# MCU1_1.net
KiCad netlist of a schematic drawn in Altium Designer
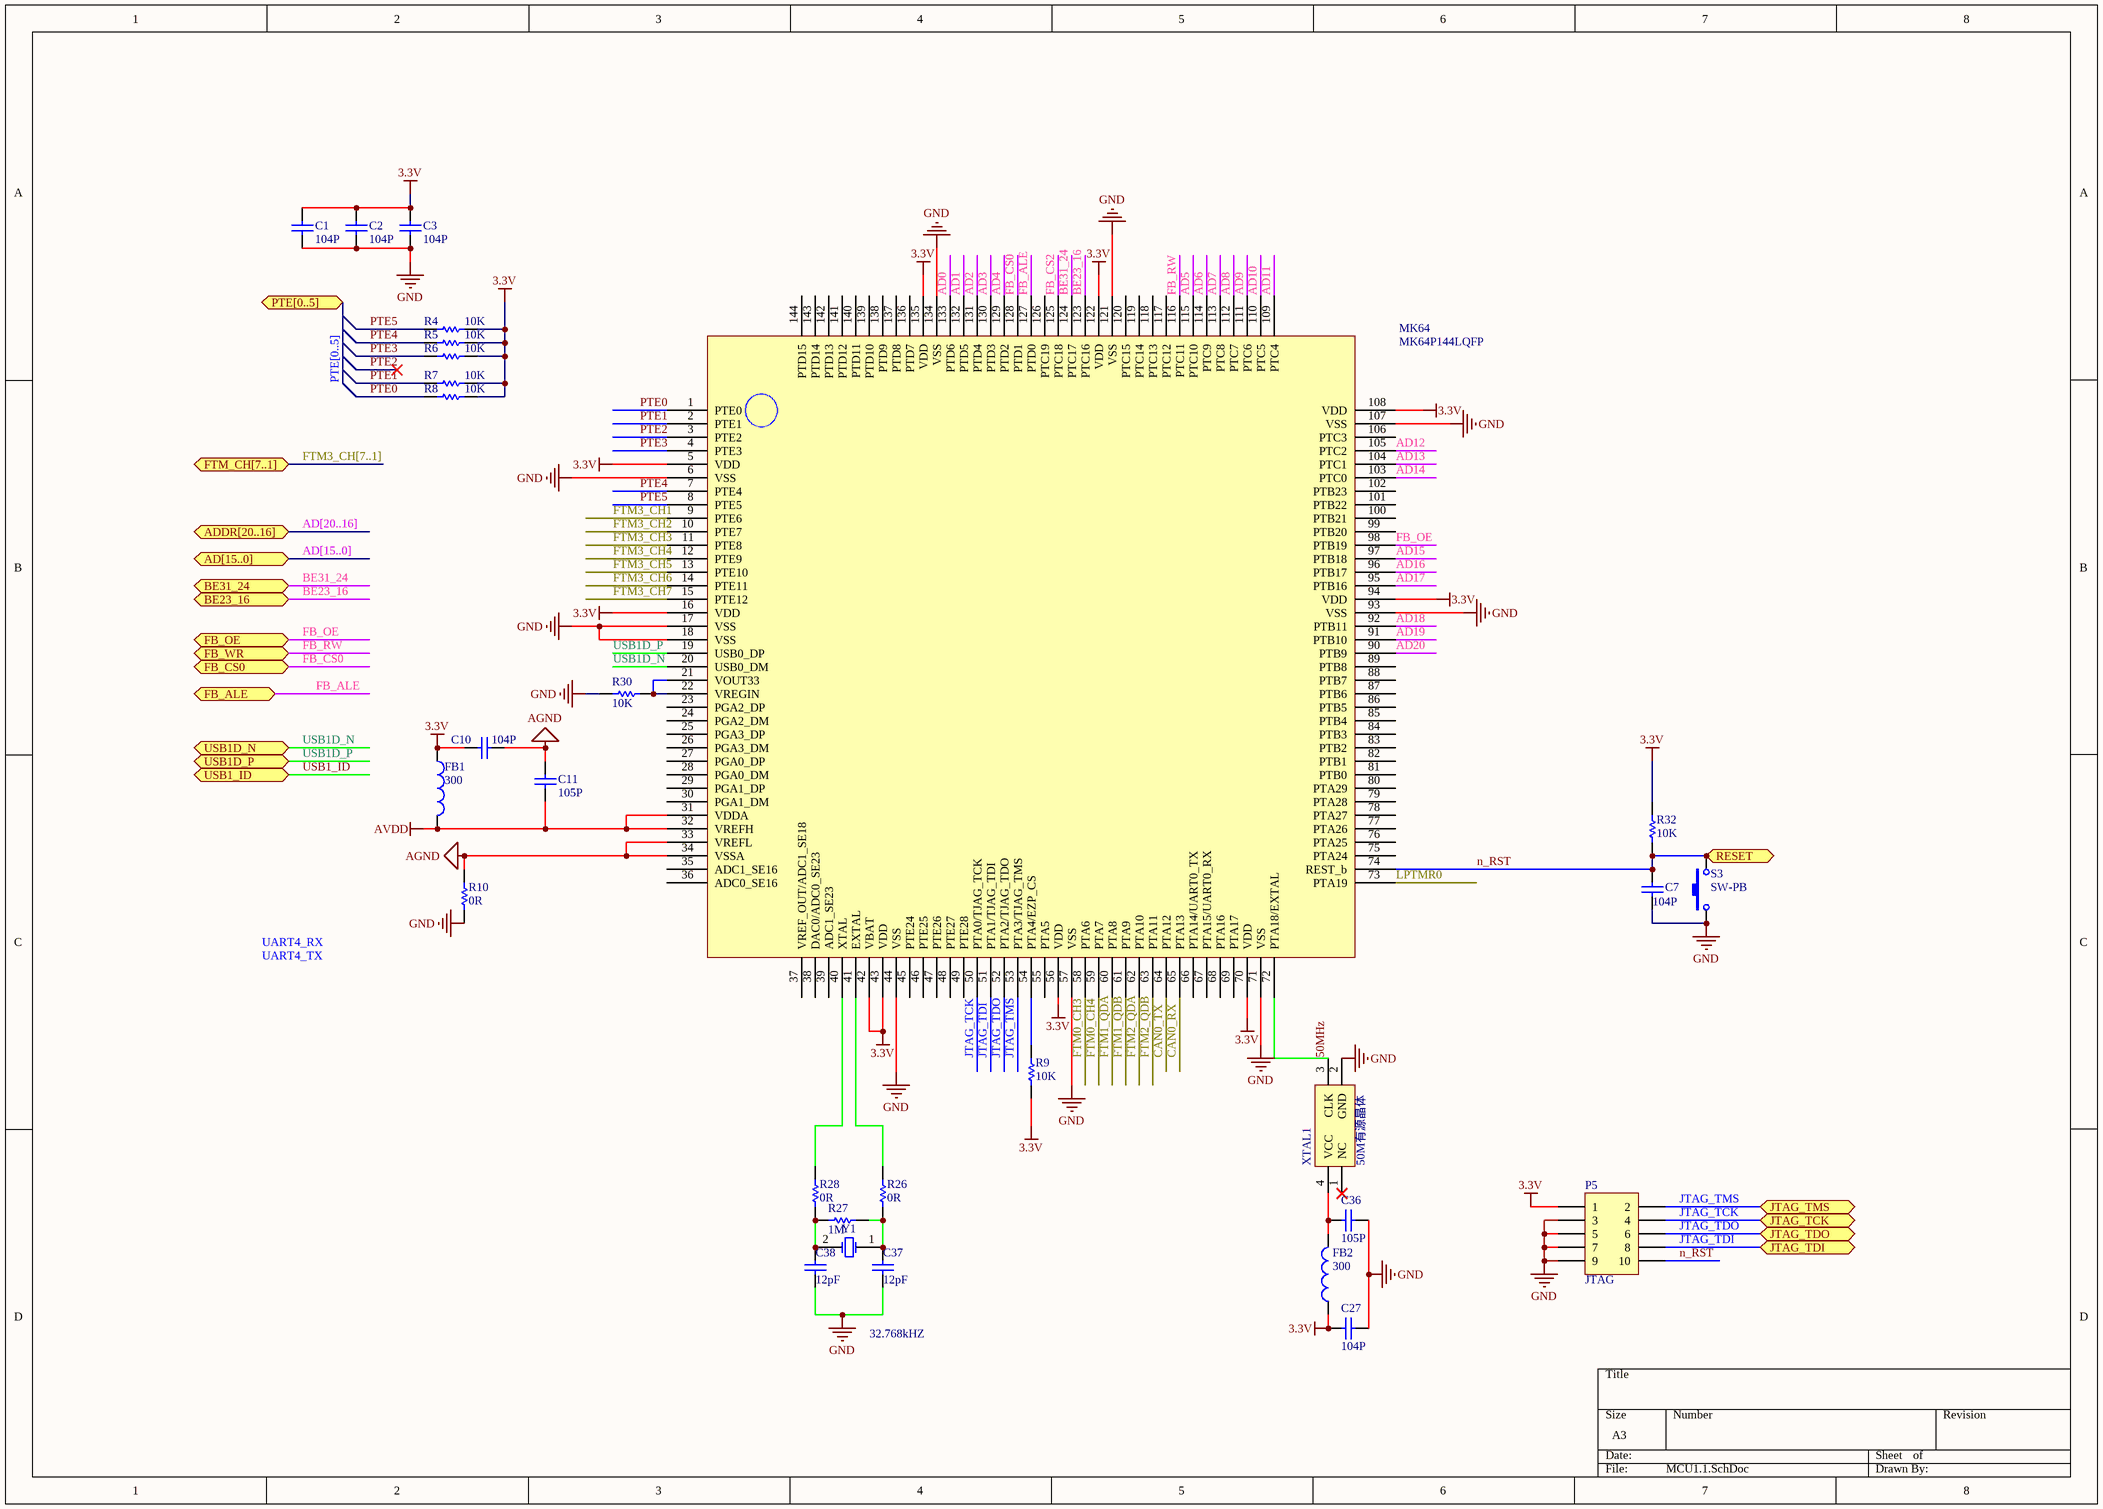
[diagram p0: MCU1.1.SchDoc]

(export (version "E")
  (design (tool "Eeschema 10.0.6"))
  (components
    (comp (ref "C1")
      (value "104P")
      (footprint "1608[0603]")
      (description "贴片电容")
      (fields (field (name "Comment") "Cap") (field (name "PUBLISHER") "Altium Limited"))
      (libsource (lib "Sparks") (part "Cap"))
    )
    (comp (ref "C2")
      (value "104P")
      (footprint "1608[0603]")
      (description "贴片电容")
      (fields (field (name "Comment") "Cap") (field (name "PUBLISHER") "Altium Limited"))
      (libsource (lib "Sparks") (part "Cap"))
    )
    (comp (ref "C3")
      (value "104P")
      (footprint "1608[0603]")
      (description "贴片电容")
      (fields (field (name "Comment") "Cap") (field (name "PUBLISHER") "Altium Limited"))
      (libsource (lib "Sparks") (part "Cap"))
    )
    (comp (ref "C7")
      (value "104P")
      (footprint "1608[0603]")
      (description "贴片电容")
      (fields (field (name "Comment") "Cap") (field (name "PUBLISHER") "Altium Limited"))
      (libsource (lib "Sparks") (part "Cap"))
    )
    (comp (ref "C10")
      (value "104P")
      (footprint "1608[0603]")
      (description "贴片电容")
      (fields (field (name "Comment") "Cap") (field (name "PUBLISHER") "Altium Limited"))
      (libsource (lib "Sparks") (part "Cap"))
    )
    (comp (ref "C11")
      (value "105P")
      (footprint "1608[0603]")
      (description "贴片电容")
      (fields (field (name "Comment") "Cap") (field (name "PUBLISHER") "Altium Limited"))
      (libsource (lib "Sparks") (part "Cap"))
    )
    (comp (ref "C27")
      (value "104P")
      (footprint "1608[0603]")
      (description "贴片电容")
      (fields (field (name "Comment") "Cap") (field (name "PUBLISHER") "Altium Limited"))
      (libsource (lib "Sparks") (part "Cap"))
    )
    (comp (ref "C36")
      (value "105P")
      (footprint "1608[0603]")
      (description "贴片电容")
      (fields (field (name "Comment") "Cap") (field (name "PUBLISHER") "Altium Limited"))
      (libsource (lib "Sparks") (part "Cap"))
    )
    (comp (ref "C37")
      (value "12pF")
      (footprint "1608[0603]")
      (description "贴片电容")
      (fields (field (name "Comment") "Cap") (field (name "PUBLISHER") "Altium Limited"))
      (libsource (lib "Sparks") (part "Cap"))
    )
    (comp (ref "C38")
      (value "12pF")
      (footprint "1608[0603]")
      (description "贴片电容")
      (fields (field (name "Comment") "Cap") (field (name "PUBLISHER") "Altium Limited"))
      (libsource (lib "Sparks") (part "Cap"))
    )
    (comp (ref "FB1")
      (value "300")
      (footprint "1608[0603]")
      (description "Inductor")
      (fields (field (name "PUBLISHER") "Altium Limited"))
      (libsource (lib "Miscellaneous Devices") (part "Inductor"))
    )
    (comp (ref "FB2")
      (value "300")
      (footprint "1608[0603]")
      (description "Inductor")
      (fields (field (name "PUBLISHER") "Altium Limited"))
      (libsource (lib "Miscellaneous Devices") (part "Inductor"))
    )
    (comp (ref "MK64")
      (value "MK64P144LQFP")
      (footprint "LQFP-144")
      (libsource (lib "2号库") (part "MK64P144LQFP"))
    )
    (comp (ref "P5")
      (value "JTAG")
      (footprint "HDR2X5")
      (description "Header, 5-Pin, Dual row")
      (fields (field (name "PUBLISHER") "Altium Limited"))
      (libsource (lib "Sparks") (part "Header 5X2"))
    )
    (comp (ref "R4")
      (value "10K")
      (footprint "1608[0603]")
      (description "贴片电阻")
      (fields (field (name "Comment") "Res") (field (name "PUBLISHER") "Altium Limited"))
      (libsource (lib "Sparks") (part "Res"))
    )
    (comp (ref "R5")
      (value "10K")
      (footprint "1608[0603]")
      (description "贴片电阻")
      (fields (field (name "Comment") "Res") (field (name "PUBLISHER") "Altium Limited"))
      (libsource (lib "Sparks") (part "Res"))
    )
    (comp (ref "R6")
      (value "10K")
      (footprint "1608[0603]")
      (description "贴片电阻")
      (fields (field (name "Comment") "Res") (field (name "PUBLISHER") "Altium Limited"))
      (libsource (lib "Sparks") (part "Res"))
    )
    (comp (ref "R7")
      (value "10K")
      (footprint "1608[0603]")
      (description "贴片电阻")
      (fields (field (name "Comment") "Res") (field (name "PUBLISHER") "Altium Limited"))
      (libsource (lib "Sparks") (part "Res"))
    )
    (comp (ref "R8")
      (value "10K")
      (footprint "1608[0603]")
      (description "贴片电阻")
      (fields (field (name "Comment") "Res") (field (name "PUBLISHER") "Altium Limited"))
      (libsource (lib "Sparks") (part "Res"))
    )
    (comp (ref "R9")
      (value "10K")
      (footprint "1608[0603]")
      (description "贴片电阻")
      (fields (field (name "Comment") "Res") (field (name "PUBLISHER") "Altium Limited"))
      (libsource (lib "Sparks") (part "Res"))
    )
    (comp (ref "R10")
      (value "0R")
      (footprint "1608[0603]")
      (description "贴片电阻")
      (fields (field (name "Comment") "Res") (field (name "PUBLISHER") "Altium Limited"))
      (libsource (lib "Sparks") (part "Res"))
    )
    (comp (ref "R26")
      (value "0R")
      (footprint "1608[0603]")
      (description "贴片电阻")
      (fields (field (name "Comment") "Res") (field (name "PUBLISHER") "Altium Limited"))
      (libsource (lib "Sparks") (part "Res"))
    )
    (comp (ref "R27")
      (value "1M")
      (footprint "1608[0603]")
      (description "贴片电阻")
      (fields (field (name "Comment") "Res") (field (name "PUBLISHER") "Altium Limited"))
      (libsource (lib "Sparks") (part "Res"))
    )
    (comp (ref "R28")
      (value "0R")
      (footprint "1608[0603]")
      (description "贴片电阻")
      (fields (field (name "Comment") "Res") (field (name "PUBLISHER") "Altium Limited"))
      (libsource (lib "Sparks") (part "Res"))
    )
    (comp (ref "R30")
      (value "10K")
      (footprint "1608[0603]")
      (description "贴片电阻")
      (fields (field (name "Comment") "Res") (field (name "PUBLISHER") "Altium Limited"))
      (libsource (lib "Sparks") (part "Res"))
    )
    (comp (ref "R32")
      (value "10K")
      (footprint "1608[0603]")
      (description "贴片电阻")
      (fields (field (name "Comment") "Res") (field (name "PUBLISHER") "Altium Limited"))
      (libsource (lib "Sparks") (part "Res"))
    )
    (comp (ref "S3")
      (value "SW-PB")
      (footprint "key 3*4*2")
      (description "Switch")
      (libsource (lib "K60-V4.0") (part "SW-PB"))
    )
    (comp (ref "XTAL1") (value "50M有源晶体") (footprint "XTAL7_3225") (libsource (lib "Sparks") (part "有源晶体")))
    (comp (ref "Y1")
      (value "32.768kHZ")
      (footprint "3215")
      (description "晶体振荡器")
      (fields (field (name "PUBLISHER") "Altium Limited"))
      (libsource (lib "Sparks") (part "XTAL"))
    )
  )
  (nets
    (net (code "1") (name "/50MHz") (class "Default")
      (node (ref "MK64") (pin "72") (pinfunction "PTA18/EXTAL_72") (pintype "passive"))
      (node (ref "XTAL1") (pin "3") (pinfunction "CLK_3") (pintype "passive"))
    )
    (net (code "2") (name "/AD0") (class "Default")
      (node (ref "MK64") (pin "133") (pinfunction "PTD6_133") (pintype "passive"))
    )
    (net (code "3") (name "/AD1") (class "Default")
      (node (ref "MK64") (pin "132") (pinfunction "PTD5_132") (pintype "passive"))
    )
    (net (code "4") (name "/AD2") (class "Default")
      (node (ref "MK64") (pin "131") (pinfunction "PTD4_131") (pintype "passive"))
    )
    (net (code "5") (name "/AD3") (class "Default")
      (node (ref "MK64") (pin "130") (pinfunction "PTD3_130") (pintype "passive"))
    )
    (net (code "6") (name "/AD4") (class "Default")
      (node (ref "MK64") (pin "129") (pinfunction "PTD2_129") (pintype "passive"))
    )
    (net (code "7") (name "/AD5") (class "Default")
      (node (ref "MK64") (pin "115") (pinfunction "PTC10_115") (pintype "passive"))
    )
    (net (code "8") (name "/AD6") (class "Default")
      (node (ref "MK64") (pin "114") (pinfunction "PTC9_114") (pintype "passive"))
    )
    (net (code "9") (name "/AD7") (class "Default")
      (node (ref "MK64") (pin "113") (pinfunction "PTC8_113") (pintype "passive"))
    )
    (net (code "10") (name "/AD8") (class "Default")
      (node (ref "MK64") (pin "112") (pinfunction "PTC7_112") (pintype "passive"))
    )
    (net (code "11") (name "/AD9") (class "Default")
      (node (ref "MK64") (pin "111") (pinfunction "PTC6_111") (pintype "passive"))
    )
    (net (code "12") (name "/AD10") (class "Default")
      (node (ref "MK64") (pin "110") (pinfunction "PTC5_110") (pintype "passive"))
    )
    (net (code "13") (name "/AD11") (class "Default")
      (node (ref "MK64") (pin "109") (pinfunction "PTC4_109") (pintype "passive"))
    )
    (net (code "14") (name "/AD12") (class "Default")
      (node (ref "MK64") (pin "105") (pinfunction "PTC2_105") (pintype "passive"))
    )
    (net (code "15") (name "/AD13") (class "Default")
      (node (ref "MK64") (pin "104") (pinfunction "PTC1_104") (pintype "passive"))
    )
    (net (code "16") (name "/AD14") (class "Default")
      (node (ref "MK64") (pin "103") (pinfunction "PTC0_103") (pintype "passive"))
    )
    (net (code "17") (name "/AD15") (class "Default")
      (node (ref "MK64") (pin "97") (pinfunction "PTB18_97") (pintype "passive"))
    )
    (net (code "18") (name "/AD16") (class "Default")
      (node (ref "MK64") (pin "96") (pinfunction "PTB17_96") (pintype "passive"))
    )
    (net (code "19") (name "/AD17") (class "Default")
      (node (ref "MK64") (pin "95") (pinfunction "PTB16_95") (pintype "passive"))
    )
    (net (code "20") (name "/AD18") (class "Default")
      (node (ref "MK64") (pin "92") (pinfunction "PTB11_92") (pintype "passive"))
    )
    (net (code "21") (name "/AD19") (class "Default")
      (node (ref "MK64") (pin "91") (pinfunction "PTB10_91") (pintype "passive"))
    )
    (net (code "22") (name "/AD20") (class "Default")
      (node (ref "MK64") (pin "90") (pinfunction "PTB9_90") (pintype "passive"))
    )
    (net (code "25") (name "/BE23_16") (class "Default")
      (node (ref "MK64") (pin "123") (pinfunction "PTC16_123") (pintype "passive"))
    )
    (net (code "26") (name "/BE31_24") (class "Default")
      (node (ref "MK64") (pin "124") (pinfunction "PTC17_124") (pintype "passive"))
    )
    (net (code "27") (name "/CAN0_RX") (class "Default")
      (node (ref "MK64") (pin "65") (pinfunction "PTA13_65") (pintype "passive"))
    )
    (net (code "28") (name "/CAN0_TX") (class "Default")
      (node (ref "MK64") (pin "64") (pinfunction "PTA12_64") (pintype "passive"))
    )
    (net (code "29") (name "/FB_ALE") (class "Default")
      (node (ref "MK64") (pin "127") (pinfunction "PTD0_127") (pintype "passive"))
    )
    (net (code "30") (name "/FB_CS0") (class "Default")
      (node (ref "MK64") (pin "128") (pinfunction "PTD1_128") (pintype "passive"))
    )
    (net (code "31") (name "/FB_CS2") (class "Default")
      (node (ref "MK64") (pin "125") (pinfunction "PTC18_125") (pintype "passive"))
    )
    (net (code "32") (name "/FB_OE") (class "Default")
      (node (ref "MK64") (pin "98") (pinfunction "PTB19_98") (pintype "passive"))
    )
    (net (code "33") (name "/FB_RW") (class "Default")
      (node (ref "MK64") (pin "116") (pinfunction "PTC11_116") (pintype "passive"))
    )
    (net (code "34") (name "/FTM0_CH3") (class "Default")
      (node (ref "MK64") (pin "58") (pinfunction "PTA6_58") (pintype "passive"))
    )
    (net (code "35") (name "/FTM0_CH4") (class "Default")
      (node (ref "MK64") (pin "59") (pinfunction "PTA7_59") (pintype "passive"))
    )
    (net (code "36") (name "/FTM1_QDA") (class "Default")
      (node (ref "MK64") (pin "60") (pinfunction "PTA8_60") (pintype "passive"))
    )
    (net (code "37") (name "/FTM1_QDB") (class "Default")
      (node (ref "MK64") (pin "61") (pinfunction "PTA9_61") (pintype "passive"))
    )
    (net (code "38") (name "/FTM2_QDA") (class "Default")
      (node (ref "MK64") (pin "62") (pinfunction "PTA10_62") (pintype "passive"))
    )
    (net (code "39") (name "/FTM2_QDB") (class "Default")
      (node (ref "MK64") (pin "63") (pinfunction "PTA11_63") (pintype "passive"))
    )
    (net (code "40") (name "/FTM3_CH1") (class "Default")
      (node (ref "MK64") (pin "9") (pinfunction "PTE6_9") (pintype "passive"))
    )
    (net (code "41") (name "/FTM3_CH2") (class "Default")
      (node (ref "MK64") (pin "10") (pinfunction "PTE7_10") (pintype "passive"))
    )
    (net (code "42") (name "/FTM3_CH3") (class "Default")
      (node (ref "MK64") (pin "11") (pinfunction "PTE8_11") (pintype "passive"))
    )
    (net (code "43") (name "/FTM3_CH4") (class "Default")
      (node (ref "MK64") (pin "12") (pinfunction "PTE9_12") (pintype "passive"))
    )
    (net (code "44") (name "/FTM3_CH5") (class "Default")
      (node (ref "MK64") (pin "13") (pinfunction "PTE10_13") (pintype "passive"))
    )
    (net (code "45") (name "/FTM3_CH6") (class "Default")
      (node (ref "MK64") (pin "14") (pinfunction "PTE11_14") (pintype "passive"))
    )
    (net (code "46") (name "/FTM3_CH7") (class "Default")
      (node (ref "MK64") (pin "15") (pinfunction "PTE12_15") (pintype "passive"))
    )
    (net (code "48") (name "/JTAG_TCK") (class "Default")
      (node (ref "MK64") (pin "50") (pinfunction "PTA0/TJAG_TCK_50") (pintype "passive"))
      (node (ref "P5") (pin "4") (pinfunction "4_4") (pintype "passive"))
    )
    (net (code "49") (name "/JTAG_TDI") (class "Default")
      (node (ref "MK64") (pin "51") (pinfunction "PTA1/TJAG_TDI_51") (pintype "passive"))
      (node (ref "P5") (pin "8") (pinfunction "8_8") (pintype "passive"))
    )
    (net (code "50") (name "/JTAG_TDO") (class "Default")
      (node (ref "MK64") (pin "52") (pinfunction "PTA2/TJAG_TDO_52") (pintype "passive"))
      (node (ref "P5") (pin "6") (pinfunction "6_6") (pintype "passive"))
    )
    (net (code "51") (name "/JTAG_TMS") (class "Default")
      (node (ref "MK64") (pin "53") (pinfunction "PTA3/TJAG_TMS_53") (pintype "passive"))
      (node (ref "P5") (pin "2") (pinfunction "2_2") (pintype "passive"))
    )
    (net (code "52") (name "/LPTMR0") (class "Default")
      (node (ref "MK64") (pin "73") (pinfunction "PTA19_73") (pintype "passive"))
    )
    (net (code "53") (name "/PTE0") (class "Default")
      (node (ref "MK64") (pin "1") (pinfunction "PTE0_1") (pintype "passive"))
      (node (ref "R8") (pin "2") (pinfunction "2_2") (pintype "passive"))
    )
    (net (code "54") (name "/PTE1") (class "Default")
      (node (ref "MK64") (pin "2") (pinfunction "PTE1_2") (pintype "passive"))
      (node (ref "R7") (pin "2") (pinfunction "2_2") (pintype "passive"))
    )
    (net (code "55") (name "/PTE2") (class "Default")
      (node (ref "MK64") (pin "3") (pinfunction "PTE2_3") (pintype "passive+no_connect"))
    )
    (net (code "56") (name "/PTE3") (class "Default")
      (node (ref "MK64") (pin "4") (pinfunction "PTE3_4") (pintype "passive"))
      (node (ref "R6") (pin "2") (pinfunction "2_2") (pintype "passive"))
    )
    (net (code "57") (name "/PTE4") (class "Default")
      (node (ref "MK64") (pin "7") (pinfunction "PTE4_7") (pintype "passive"))
      (node (ref "R5") (pin "2") (pinfunction "2_2") (pintype "passive"))
    )
    (net (code "58") (name "/PTE5") (class "Default")
      (node (ref "MK64") (pin "8") (pinfunction "PTE5_8") (pintype "passive"))
      (node (ref "R4") (pin "2") (pinfunction "2_2") (pintype "passive"))
    )
    (net (code "62") (name "/USB1D_N") (class "Default")
      (node (ref "MK64") (pin "20") (pinfunction "USB0_DM_20") (pintype "passive"))
    )
    (net (code "63") (name "/USB1D_P") (class "Default")
      (node (ref "MK64") (pin "19") (pinfunction "USB0_DP_19") (pintype "passive"))
    )
    (net (code "65") (name "/n_RST") (class "Default")
      (node (ref "C7") (pin "2") (pinfunction "2_2") (pintype "passive"))
      (node (ref "MK64") (pin "74") (pinfunction "REST_b_74") (pintype "passive"))
      (node (ref "P5") (pin "10") (pinfunction "10_10") (pintype "passive"))
      (node (ref "R32") (pin "2") (pinfunction "2_2") (pintype "passive"))
      (node (ref "S3") (pin "2") (pinfunction "2_2") (pintype "passive"))
    )
    (net (code "66") (name "3.3V") (class "Default")
      (node (ref "C1") (pin "2") (pinfunction "2_2") (pintype "passive"))
      (node (ref "C10") (pin "1") (pinfunction "1_1") (pintype "passive"))
      (node (ref "C2") (pin "2") (pinfunction "2_2") (pintype "passive"))
      (node (ref "C27") (pin "2") (pinfunction "2_2") (pintype "passive"))
      (node (ref "C3") (pin "2") (pinfunction "2_2") (pintype "passive"))
      (node (ref "FB1") (pin "1") (pinfunction "1_1") (pintype "passive"))
      (node (ref "FB2") (pin "1") (pinfunction "1_1") (pintype "passive"))
      (node (ref "MK64") (pin "108") (pinfunction "VDD_108") (pintype "passive"))
      (node (ref "MK64") (pin "122") (pinfunction "VDD_122") (pintype "passive"))
      (node (ref "MK64") (pin "135") (pinfunction "VDD_135") (pintype "passive"))
      (node (ref "MK64") (pin "16") (pinfunction "VDD_16") (pintype "passive"))
      (node (ref "MK64") (pin "42") (pinfunction "VBAT_42") (pintype "passive"))
      (node (ref "MK64") (pin "43") (pinfunction "VDD_43") (pintype "passive"))
      (node (ref "MK64") (pin "5") (pinfunction "VDD_5") (pintype "passive"))
      (node (ref "MK64") (pin "56") (pinfunction "VDD_56") (pintype "passive"))
      (node (ref "MK64") (pin "70") (pinfunction "VDD_70") (pintype "passive"))
      (node (ref "MK64") (pin "94") (pinfunction "VDD_94") (pintype "passive"))
      (node (ref "P5") (pin "1") (pinfunction "1_1") (pintype "passive"))
      (node (ref "R32") (pin "1") (pinfunction "1_1") (pintype "passive"))
      (node (ref "R4") (pin "1") (pinfunction "1_1") (pintype "passive"))
      (node (ref "R5") (pin "1") (pinfunction "1_1") (pintype "passive"))
      (node (ref "R6") (pin "1") (pinfunction "1_1") (pintype "passive"))
      (node (ref "R7") (pin "1") (pinfunction "1_1") (pintype "passive"))
      (node (ref "R8") (pin "1") (pinfunction "1_1") (pintype "passive"))
      (node (ref "R9") (pin "1") (pinfunction "1_1") (pintype "passive"))
    )
    (net (code "67") (name "AGND") (class "Default")
      (node (ref "C10") (pin "2") (pinfunction "2_2") (pintype "passive"))
      (node (ref "C11") (pin "2") (pinfunction "2_2") (pintype "passive"))
      (node (ref "MK64") (pin "33") (pinfunction "VREFL_33") (pintype "passive"))
      (node (ref "MK64") (pin "34") (pinfunction "VSSA_34") (pintype "passive"))
      (node (ref "R10") (pin "2") (pinfunction "2_2") (pintype "passive"))
    )
    (net (code "68") (name "AVDD") (class "Default")
      (node (ref "C11") (pin "1") (pinfunction "1_1") (pintype "passive"))
      (node (ref "FB1") (pin "2") (pinfunction "2_2") (pintype "passive"))
      (node (ref "MK64") (pin "31") (pinfunction "VDDA_31") (pintype "passive"))
      (node (ref "MK64") (pin "32") (pinfunction "VREFH_32") (pintype "passive"))
    )
    (net (code "69") (name "GND") (class "Default")
      (node (ref "C1") (pin "1") (pinfunction "1_1") (pintype "passive"))
      (node (ref "C2") (pin "1") (pinfunction "1_1") (pintype "passive"))
      (node (ref "C27") (pin "1") (pinfunction "1_1") (pintype "passive"))
      (node (ref "C3") (pin "1") (pinfunction "1_1") (pintype "passive"))
      (node (ref "C36") (pin "1") (pinfunction "1_1") (pintype "passive"))
      (node (ref "C37") (pin "1") (pinfunction "1_1") (pintype "passive"))
      (node (ref "C38") (pin "1") (pinfunction "1_1") (pintype "passive"))
      (node (ref "C7") (pin "1") (pinfunction "1_1") (pintype "passive"))
      (node (ref "MK64") (pin "107") (pinfunction "VSS_107") (pintype "passive"))
      (node (ref "MK64") (pin "121") (pinfunction "VSS_121") (pintype "passive"))
      (node (ref "MK64") (pin "134") (pinfunction "VSS_134") (pintype "passive"))
      (node (ref "MK64") (pin "17") (pinfunction "VSS_17") (pintype "passive"))
      (node (ref "MK64") (pin "18") (pinfunction "VSS_18") (pintype "passive"))
      (node (ref "MK64") (pin "44") (pinfunction "VSS_44") (pintype "passive"))
      (node (ref "MK64") (pin "57") (pinfunction "VSS_57") (pintype "passive"))
      (node (ref "MK64") (pin "6") (pinfunction "VSS_6") (pintype "passive"))
      (node (ref "MK64") (pin "71") (pinfunction "VSS_71") (pintype "passive"))
      (node (ref "MK64") (pin "93") (pinfunction "VSS_93") (pintype "passive"))
      (node (ref "P5") (pin "3") (pinfunction "3_3") (pintype "passive"))
      (node (ref "P5") (pin "5") (pinfunction "5_5") (pintype "passive"))
      (node (ref "P5") (pin "7") (pinfunction "7_7") (pintype "passive"))
      (node (ref "P5") (pin "9") (pinfunction "9_9") (pintype "passive"))
      (node (ref "R10") (pin "1") (pinfunction "1_1") (pintype "passive"))
      (node (ref "R30") (pin "1") (pinfunction "1_1") (pintype "passive"))
      (node (ref "S3") (pin "1") (pinfunction "1_1") (pintype "passive"))
      (node (ref "XTAL1") (pin "2") (pinfunction "GND_2") (pintype "passive"))
    )
    (net (code "70") (name "Net-(MK64-EXTAL)") (class "Default")
      (node (ref "MK64") (pin "41") (pinfunction "EXTAL_41") (pintype "passive"))
      (node (ref "R26") (pin "2") (pinfunction "2_2") (pintype "passive"))
    )
    (net (code "71") (name "Net-(MK64-PTA4{slash}EZP_CS)") (class "Default")
      (node (ref "MK64") (pin "54") (pinfunction "PTA4/EZP_CS_54") (pintype "passive"))
      (node (ref "R9") (pin "2") (pinfunction "2_2") (pintype "passive"))
    )
    (net (code "72") (name "Net-(MK64-VOUT33)") (class "Default")
      (node (ref "MK64") (pin "21") (pinfunction "VOUT33_21") (pintype "passive"))
      (node (ref "MK64") (pin "22") (pinfunction "VREGIN_22") (pintype "passive"))
      (node (ref "R30") (pin "2") (pinfunction "2_2") (pintype "passive"))
    )
    (net (code "73") (name "Net-(MK64-XTAL)") (class "Default")
      (node (ref "MK64") (pin "40") (pinfunction "XTAL_40") (pintype "passive"))
      (node (ref "R28") (pin "2") (pinfunction "2_2") (pintype "passive"))
    )
    (net (code "74") (name "Net-(XTAL1-VCC)") (class "Default")
      (node (ref "C36") (pin "2") (pinfunction "2_2") (pintype "passive"))
      (node (ref "FB2") (pin "2") (pinfunction "2_2") (pintype "passive"))
      (node (ref "XTAL1") (pin "4") (pinfunction "VCC_4") (pintype "passive"))
    )
    (net (code "75") (name "Net-(Y1-OSC1)") (class "Default")
      (node (ref "C37") (pin "2") (pinfunction "2_2") (pintype "passive"))
      (node (ref "R26") (pin "1") (pinfunction "1_1") (pintype "passive"))
      (node (ref "R27") (pin "1") (pinfunction "1_1") (pintype "passive"))
      (node (ref "Y1") (pin "1") (pinfunction "OSC1_1") (pintype "passive"))
    )
    (net (code "76") (name "Net-(Y1-OSC2)") (class "Default")
      (node (ref "C38") (pin "2") (pinfunction "2_2") (pintype "passive"))
      (node (ref "R27") (pin "2") (pinfunction "2_2") (pintype "passive"))
      (node (ref "R28") (pin "1") (pinfunction "1_1") (pintype "passive"))
      (node (ref "Y1") (pin "2") (pinfunction "OSC2_2") (pintype "passive"))
    )
    (net (code "77") (name "unconnected-(MK64-ADC0_SE16-Pad36)") (class "Default")
      (node (ref "MK64") (pin "36") (pinfunction "ADC0_SE16_36") (pintype "passive"))
    )
    (net (code "78") (name "unconnected-(MK64-ADC1_SE16-Pad35)") (class "Default")
      (node (ref "MK64") (pin "35") (pinfunction "ADC1_SE16_35") (pintype "passive"))
    )
    (net (code "79") (name "unconnected-(MK64-ADC1_SE23-Pad39)") (class "Default")
      (node (ref "MK64") (pin "39") (pinfunction "ADC1_SE23_39") (pintype "passive"))
    )
    (net (code "80") (name "unconnected-(MK64-DAC0{slash}ADC0_SE23-Pad38)") (class "Default")
      (node (ref "MK64") (pin "38") (pinfunction "DAC0/ADC0_SE23_38") (pintype "passive"))
    )
    (net (code "81") (name "unconnected-(MK64-PGA0_DM-Pad28)") (class "Default")
      (node (ref "MK64") (pin "28") (pinfunction "PGA0_DM_28") (pintype "passive"))
    )
    (net (code "82") (name "unconnected-(MK64-PGA0_DP-Pad27)") (class "Default")
      (node (ref "MK64") (pin "27") (pinfunction "PGA0_DP_27") (pintype "passive"))
    )
    (net (code "83") (name "unconnected-(MK64-PGA1_DM-Pad30)") (class "Default")
      (node (ref "MK64") (pin "30") (pinfunction "PGA1_DM_30") (pintype "passive"))
    )
    (net (code "84") (name "unconnected-(MK64-PGA1_DP-Pad29)") (class "Default")
      (node (ref "MK64") (pin "29") (pinfunction "PGA1_DP_29") (pintype "passive"))
    )
    (net (code "85") (name "unconnected-(MK64-PGA2_DM-Pad24)") (class "Default")
      (node (ref "MK64") (pin "24") (pinfunction "PGA2_DM_24") (pintype "passive"))
    )
    (net (code "86") (name "unconnected-(MK64-PGA2_DP-Pad23)") (class "Default")
      (node (ref "MK64") (pin "23") (pinfunction "PGA2_DP_23") (pintype "passive"))
    )
    (net (code "87") (name "unconnected-(MK64-PGA3_DM-Pad26)") (class "Default")
      (node (ref "MK64") (pin "26") (pinfunction "PGA3_DM_26") (pintype "passive"))
    )
    (net (code "88") (name "unconnected-(MK64-PGA3_DP-Pad25)") (class "Default")
      (node (ref "MK64") (pin "25") (pinfunction "PGA3_DP_25") (pintype "passive"))
    )
    (net (code "89") (name "unconnected-(MK64-PTA5-Pad55)") (class "Default")
      (node (ref "MK64") (pin "55") (pinfunction "PTA5_55") (pintype "passive"))
    )
    (net (code "90") (name "unconnected-(MK64-PTA14{slash}UART0_TX-Pad66)") (class "Default")
      (node (ref "MK64") (pin "66") (pinfunction "PTA14/UART0_TX_66") (pintype "passive"))
    )
    (net (code "91") (name "unconnected-(MK64-PTA15{slash}UART0_RX-Pad67)") (class "Default")
      (node (ref "MK64") (pin "67") (pinfunction "PTA15/UART0_RX_67") (pintype "passive"))
    )
    (net (code "92") (name "unconnected-(MK64-PTA16-Pad68)") (class "Default")
      (node (ref "MK64") (pin "68") (pinfunction "PTA16_68") (pintype "passive"))
    )
    (net (code "93") (name "unconnected-(MK64-PTA17-Pad69)") (class "Default")
      (node (ref "MK64") (pin "69") (pinfunction "PTA17_69") (pintype "passive"))
    )
    (net (code "94") (name "unconnected-(MK64-PTA24-Pad75)") (class "Default")
      (node (ref "MK64") (pin "75") (pinfunction "PTA24_75") (pintype "passive"))
    )
    (net (code "95") (name "unconnected-(MK64-PTA25-Pad76)") (class "Default")
      (node (ref "MK64") (pin "76") (pinfunction "PTA25_76") (pintype "passive"))
    )
    (net (code "96") (name "unconnected-(MK64-PTA26-Pad77)") (class "Default")
      (node (ref "MK64") (pin "77") (pinfunction "PTA26_77") (pintype "passive"))
    )
    (net (code "97") (name "unconnected-(MK64-PTA27-Pad78)") (class "Default")
      (node (ref "MK64") (pin "78") (pinfunction "PTA27_78") (pintype "passive"))
    )
    (net (code "98") (name "unconnected-(MK64-PTA28-Pad79)") (class "Default")
      (node (ref "MK64") (pin "79") (pinfunction "PTA28_79") (pintype "passive"))
    )
    (net (code "99") (name "unconnected-(MK64-PTA29-Pad80)") (class "Default")
      (node (ref "MK64") (pin "80") (pinfunction "PTA29_80") (pintype "passive"))
    )
    (net (code "100") (name "unconnected-(MK64-PTB0-Pad81)") (class "Default")
      (node (ref "MK64") (pin "81") (pinfunction "PTB0_81") (pintype "passive"))
    )
    (net (code "101") (name "unconnected-(MK64-PTB1-Pad82)") (class "Default")
      (node (ref "MK64") (pin "82") (pinfunction "PTB1_82") (pintype "passive"))
    )
    (net (code "102") (name "unconnected-(MK64-PTB2-Pad83)") (class "Default")
      (node (ref "MK64") (pin "83") (pinfunction "PTB2_83") (pintype "passive"))
    )
    (net (code "103") (name "unconnected-(MK64-PTB3-Pad84)") (class "Default")
      (node (ref "MK64") (pin "84") (pinfunction "PTB3_84") (pintype "passive"))
    )
    (net (code "104") (name "unconnected-(MK64-PTB4-Pad85)") (class "Default")
      (node (ref "MK64") (pin "85") (pinfunction "PTB4_85") (pintype "passive"))
    )
    (net (code "105") (name "unconnected-(MK64-PTB5-Pad86)") (class "Default")
      (node (ref "MK64") (pin "86") (pinfunction "PTB5_86") (pintype "passive"))
    )
    (net (code "106") (name "unconnected-(MK64-PTB6-Pad87)") (class "Default")
      (node (ref "MK64") (pin "87") (pinfunction "PTB6_87") (pintype "passive"))
    )
    (net (code "107") (name "unconnected-(MK64-PTB7-Pad88)") (class "Default")
      (node (ref "MK64") (pin "88") (pinfunction "PTB7_88") (pintype "passive"))
    )
    (net (code "108") (name "unconnected-(MK64-PTB8-Pad89)") (class "Default")
      (node (ref "MK64") (pin "89") (pinfunction "PTB8_89") (pintype "passive"))
    )
    (net (code "109") (name "unconnected-(MK64-PTB20-Pad99)") (class "Default")
      (node (ref "MK64") (pin "99") (pinfunction "PTB20_99") (pintype "passive"))
    )
    (net (code "110") (name "unconnected-(MK64-PTB21-Pad100)") (class "Default")
      (node (ref "MK64") (pin "100") (pinfunction "PTB21_100") (pintype "passive"))
    )
    (net (code "111") (name "unconnected-(MK64-PTB22-Pad101)") (class "Default")
      (node (ref "MK64") (pin "101") (pinfunction "PTB22_101") (pintype "passive"))
    )
    (net (code "112") (name "unconnected-(MK64-PTB23-Pad102)") (class "Default")
      (node (ref "MK64") (pin "102") (pinfunction "PTB23_102") (pintype "passive"))
    )
    (net (code "113") (name "unconnected-(MK64-PTC3-Pad106)") (class "Default")
      (node (ref "MK64") (pin "106") (pinfunction "PTC3_106") (pintype "passive"))
    )
    (net (code "114") (name "unconnected-(MK64-PTC12-Pad117)") (class "Default")
      (node (ref "MK64") (pin "117") (pinfunction "PTC12_117") (pintype "passive"))
    )
    (net (code "115") (name "unconnected-(MK64-PTC13-Pad118)") (class "Default")
      (node (ref "MK64") (pin "118") (pinfunction "PTC13_118") (pintype "passive"))
    )
    (net (code "116") (name "unconnected-(MK64-PTC14-Pad119)") (class "Default")
      (node (ref "MK64") (pin "119") (pinfunction "PTC14_119") (pintype "passive"))
    )
    (net (code "117") (name "unconnected-(MK64-PTC15-Pad120)") (class "Default")
      (node (ref "MK64") (pin "120") (pinfunction "PTC15_120") (pintype "passive"))
    )
    (net (code "118") (name "unconnected-(MK64-PTC19-Pad126)") (class "Default")
      (node (ref "MK64") (pin "126") (pinfunction "PTC19_126") (pintype "passive"))
    )
    (net (code "119") (name "unconnected-(MK64-PTD7-Pad136)") (class "Default")
      (node (ref "MK64") (pin "136") (pinfunction "PTD7_136") (pintype "passive"))
    )
    (net (code "120") (name "unconnected-(MK64-PTD8-Pad137)") (class "Default")
      (node (ref "MK64") (pin "137") (pinfunction "PTD8_137") (pintype "passive"))
    )
    (net (code "121") (name "unconnected-(MK64-PTD9-Pad138)") (class "Default")
      (node (ref "MK64") (pin "138") (pinfunction "PTD9_138") (pintype "passive"))
    )
    (net (code "122") (name "unconnected-(MK64-PTD10-Pad139)") (class "Default")
      (node (ref "MK64") (pin "139") (pinfunction "PTD10_139") (pintype "passive"))
    )
    (net (code "123") (name "unconnected-(MK64-PTD11-Pad140)") (class "Default")
      (node (ref "MK64") (pin "140") (pinfunction "PTD11_140") (pintype "passive"))
    )
    (net (code "124") (name "unconnected-(MK64-PTD12-Pad141)") (class "Default")
      (node (ref "MK64") (pin "141") (pinfunction "PTD12_141") (pintype "passive"))
    )
    (net (code "125") (name "unconnected-(MK64-PTD13-Pad142)") (class "Default")
      (node (ref "MK64") (pin "142") (pinfunction "PTD13_142") (pintype "passive"))
    )
    (net (code "126") (name "unconnected-(MK64-PTD14-Pad143)") (class "Default")
      (node (ref "MK64") (pin "143") (pinfunction "PTD14_143") (pintype "passive"))
    )
    (net (code "127") (name "unconnected-(MK64-PTD15-Pad144)") (class "Default")
      (node (ref "MK64") (pin "144") (pinfunction "PTD15_144") (pintype "passive"))
    )
    (net (code "128") (name "unconnected-(MK64-PTE24-Pad45)") (class "Default")
      (node (ref "MK64") (pin "45") (pinfunction "PTE24_45") (pintype "passive"))
    )
    (net (code "129") (name "unconnected-(MK64-PTE25-Pad46)") (class "Default")
      (node (ref "MK64") (pin "46") (pinfunction "PTE25_46") (pintype "passive"))
    )
    (net (code "130") (name "unconnected-(MK64-PTE26-Pad47)") (class "Default")
      (node (ref "MK64") (pin "47") (pinfunction "PTE26_47") (pintype "passive"))
    )
    (net (code "131") (name "unconnected-(MK64-PTE27-Pad48)") (class "Default")
      (node (ref "MK64") (pin "48") (pinfunction "PTE27_48") (pintype "passive"))
    )
    (net (code "132") (name "unconnected-(MK64-PTE28-Pad49)") (class "Default")
      (node (ref "MK64") (pin "49") (pinfunction "PTE28_49") (pintype "passive"))
    )
    (net (code "133") (name "unconnected-(MK64-VREF_OUT{slash}ADC1_SE18-Pad37)") (class "Default")
      (node (ref "MK64") (pin "37") (pinfunction "VREF_OUT/ADC1_SE18_37") (pintype "passive"))
    )
    (net (code "134") (name "unconnected-(XTAL1-NC-Pad1)") (class "Default")
      (node (ref "XTAL1") (pin "1") (pinfunction "NC_1") (pintype "passive+no_connect"))
    )
  )
)
